# LED-Lamp-pth.net
KiCad netlist of a schematic drawn in EAGLE
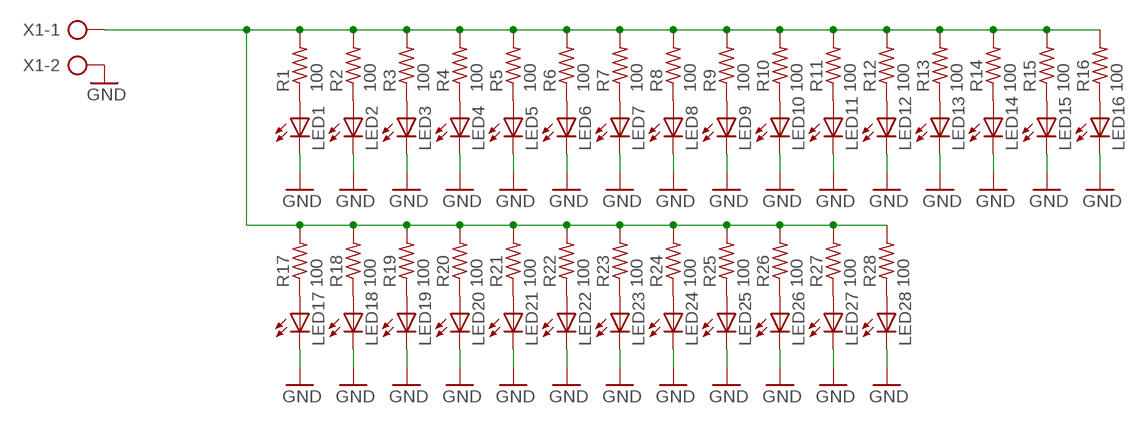
[diagram p0: schematic, sheet 1]

(export (version "E")
  (design (tool "Eeschema 10.0.6"))
  (components
    (comp (ref "LED1")
      (value "LEDSML0805")
      (footprint "eagle-import:SML0805")
      (libsource (lib "eagle-import") (part "LEDSML0805"))
    )
    (comp (ref "LED2")
      (value "LEDSML0805")
      (footprint "eagle-import:SML0805")
      (libsource (lib "eagle-import") (part "LEDSML0805"))
    )
    (comp (ref "LED3")
      (value "LEDSML0805")
      (footprint "eagle-import:SML0805")
      (libsource (lib "eagle-import") (part "LEDSML0805"))
    )
    (comp (ref "LED4")
      (value "LEDSML0805")
      (footprint "eagle-import:SML0805")
      (libsource (lib "eagle-import") (part "LEDSML0805"))
    )
    (comp (ref "LED5")
      (value "LEDSML0805")
      (footprint "eagle-import:SML0805")
      (libsource (lib "eagle-import") (part "LEDSML0805"))
    )
    (comp (ref "LED6")
      (value "LEDSML0805")
      (footprint "eagle-import:SML0805")
      (libsource (lib "eagle-import") (part "LEDSML0805"))
    )
    (comp (ref "LED7")
      (value "LEDSML0805")
      (footprint "eagle-import:SML0805")
      (libsource (lib "eagle-import") (part "LEDSML0805"))
    )
    (comp (ref "LED8")
      (value "LEDSML0805")
      (footprint "eagle-import:SML0805")
      (libsource (lib "eagle-import") (part "LEDSML0805"))
    )
    (comp (ref "LED9")
      (value "LEDSML0805")
      (footprint "eagle-import:SML0805")
      (libsource (lib "eagle-import") (part "LEDSML0805"))
    )
    (comp (ref "LED10")
      (value "LEDSML0805")
      (footprint "eagle-import:SML0805")
      (libsource (lib "eagle-import") (part "LEDSML0805"))
    )
    (comp (ref "LED11")
      (value "LEDSML0805")
      (footprint "eagle-import:SML0805")
      (libsource (lib "eagle-import") (part "LEDSML0805"))
    )
    (comp (ref "LED12")
      (value "LEDSML0805")
      (footprint "eagle-import:SML0805")
      (libsource (lib "eagle-import") (part "LEDSML0805"))
    )
    (comp (ref "LED13")
      (value "LEDSML0805")
      (footprint "eagle-import:SML0805")
      (libsource (lib "eagle-import") (part "LEDSML0805"))
    )
    (comp (ref "LED14")
      (value "LEDSML0805")
      (footprint "eagle-import:SML0805")
      (libsource (lib "eagle-import") (part "LEDSML0805"))
    )
    (comp (ref "LED15")
      (value "LEDSML0805")
      (footprint "eagle-import:SML0805")
      (libsource (lib "eagle-import") (part "LEDSML0805"))
    )
    (comp (ref "LED16")
      (value "LEDSML0805")
      (footprint "eagle-import:SML0805")
      (libsource (lib "eagle-import") (part "LEDSML0805"))
    )
    (comp (ref "LED17")
      (value "LEDSML0805")
      (footprint "eagle-import:SML0805")
      (libsource (lib "eagle-import") (part "LEDSML0805"))
    )
    (comp (ref "LED18")
      (value "LEDSML0805")
      (footprint "eagle-import:SML0805")
      (libsource (lib "eagle-import") (part "LEDSML0805"))
    )
    (comp (ref "LED19")
      (value "LEDSML0805")
      (footprint "eagle-import:SML0805")
      (libsource (lib "eagle-import") (part "LEDSML0805"))
    )
    (comp (ref "LED20")
      (value "LEDSML0805")
      (footprint "eagle-import:SML0805")
      (libsource (lib "eagle-import") (part "LEDSML0805"))
    )
    (comp (ref "LED21")
      (value "LEDSML0805")
      (footprint "eagle-import:SML0805")
      (libsource (lib "eagle-import") (part "LEDSML0805"))
    )
    (comp (ref "LED22")
      (value "LEDSML0805")
      (footprint "eagle-import:SML0805")
      (libsource (lib "eagle-import") (part "LEDSML0805"))
    )
    (comp (ref "LED23")
      (value "LEDSML0805")
      (footprint "eagle-import:SML0805")
      (libsource (lib "eagle-import") (part "LEDSML0805"))
    )
    (comp (ref "LED24")
      (value "LEDSML0805")
      (footprint "eagle-import:SML0805")
      (libsource (lib "eagle-import") (part "LEDSML0805"))
    )
    (comp (ref "LED25")
      (value "LEDSML0805")
      (footprint "eagle-import:SML0805")
      (libsource (lib "eagle-import") (part "LEDSML0805"))
    )
    (comp (ref "LED26")
      (value "LEDSML0805")
      (footprint "eagle-import:SML0805")
      (libsource (lib "eagle-import") (part "LEDSML0805"))
    )
    (comp (ref "LED27")
      (value "LEDSML0805")
      (footprint "eagle-import:SML0805")
      (libsource (lib "eagle-import") (part "LEDSML0805"))
    )
    (comp (ref "LED28")
      (value "LEDSML0805")
      (footprint "eagle-import:SML0805")
      (libsource (lib "eagle-import") (part "LEDSML0805"))
    )
    (comp (ref "R1")
      (value "100")
      (footprint "eagle-import:0207_7")
      (libsource (lib "eagle-import") (part "R-US_0207/7"))
    )
    (comp (ref "R2")
      (value "100")
      (footprint "eagle-import:0207_7")
      (libsource (lib "eagle-import") (part "R-US_0207/7"))
    )
    (comp (ref "R3")
      (value "100")
      (footprint "eagle-import:0207_7")
      (libsource (lib "eagle-import") (part "R-US_0207/7"))
    )
    (comp (ref "R4")
      (value "100")
      (footprint "eagle-import:0207_7")
      (libsource (lib "eagle-import") (part "R-US_0207/7"))
    )
    (comp (ref "R5")
      (value "100")
      (footprint "eagle-import:0207_7")
      (libsource (lib "eagle-import") (part "R-US_0207/7"))
    )
    (comp (ref "R6")
      (value "100")
      (footprint "eagle-import:0207_7")
      (libsource (lib "eagle-import") (part "R-US_0207/7"))
    )
    (comp (ref "R7")
      (value "100")
      (footprint "eagle-import:0207_7")
      (libsource (lib "eagle-import") (part "R-US_0207/7"))
    )
    (comp (ref "R8")
      (value "100")
      (footprint "eagle-import:0207_7")
      (libsource (lib "eagle-import") (part "R-US_0207/7"))
    )
    (comp (ref "R9")
      (value "100")
      (footprint "eagle-import:0207_7")
      (libsource (lib "eagle-import") (part "R-US_0207/7"))
    )
    (comp (ref "R10")
      (value "100")
      (footprint "eagle-import:0207_7")
      (libsource (lib "eagle-import") (part "R-US_0207/7"))
    )
    (comp (ref "R11")
      (value "100")
      (footprint "eagle-import:0207_7")
      (libsource (lib "eagle-import") (part "R-US_0207/7"))
    )
    (comp (ref "R12")
      (value "100")
      (footprint "eagle-import:0207_7")
      (libsource (lib "eagle-import") (part "R-US_0207/7"))
    )
    (comp (ref "R13")
      (value "100")
      (footprint "eagle-import:0207_7")
      (libsource (lib "eagle-import") (part "R-US_0207/7"))
    )
    (comp (ref "R14")
      (value "100")
      (footprint "eagle-import:0207_7")
      (libsource (lib "eagle-import") (part "R-US_0207/7"))
    )
    (comp (ref "R15")
      (value "100")
      (footprint "eagle-import:0207_7")
      (libsource (lib "eagle-import") (part "R-US_0207/7"))
    )
    (comp (ref "R16")
      (value "100")
      (footprint "eagle-import:0207_7")
      (libsource (lib "eagle-import") (part "R-US_0207/7"))
    )
    (comp (ref "R17")
      (value "100")
      (footprint "eagle-import:0207_7")
      (libsource (lib "eagle-import") (part "R-US_0207/7"))
    )
    (comp (ref "R18")
      (value "100")
      (footprint "eagle-import:0207_7")
      (libsource (lib "eagle-import") (part "R-US_0207/7"))
    )
    (comp (ref "R19")
      (value "100")
      (footprint "eagle-import:0207_7")
      (libsource (lib "eagle-import") (part "R-US_0207/7"))
    )
    (comp (ref "R20")
      (value "100")
      (footprint "eagle-import:0207_7")
      (libsource (lib "eagle-import") (part "R-US_0207/7"))
    )
    (comp (ref "R21")
      (value "100")
      (footprint "eagle-import:0207_7")
      (libsource (lib "eagle-import") (part "R-US_0207/7"))
    )
    (comp (ref "R22")
      (value "100")
      (footprint "eagle-import:0207_7")
      (libsource (lib "eagle-import") (part "R-US_0207/7"))
    )
    (comp (ref "R23")
      (value "100")
      (footprint "eagle-import:0207_7")
      (libsource (lib "eagle-import") (part "R-US_0207/7"))
    )
    (comp (ref "R24")
      (value "100")
      (footprint "eagle-import:0207_7")
      (libsource (lib "eagle-import") (part "R-US_0207/7"))
    )
    (comp (ref "R25")
      (value "100")
      (footprint "eagle-import:0207_7")
      (libsource (lib "eagle-import") (part "R-US_0207/7"))
    )
    (comp (ref "R26")
      (value "100")
      (footprint "eagle-import:0207_7")
      (libsource (lib "eagle-import") (part "R-US_0207/7"))
    )
    (comp (ref "R27")
      (value "100")
      (footprint "eagle-import:0207_7")
      (libsource (lib "eagle-import") (part "R-US_0207/7"))
    )
    (comp (ref "R28")
      (value "100")
      (footprint "eagle-import:0207_7")
      (libsource (lib "eagle-import") (part "R-US_0207/7"))
    )
    (comp (ref "X1")
      (value "AK300/2")
      (footprint "eagle-import:AK300_2")
      (libsource (lib "eagle-import") (part "AK300/2"))
    )
  )
  (nets
    (net (code "1") (name "GND") (class "Default")
      (node (ref "LED1") (pin "C") (pinfunction "C_C") (pintype "passive"))
      (node (ref "LED10") (pin "C") (pinfunction "C_C") (pintype "passive"))
      (node (ref "LED11") (pin "C") (pinfunction "C_C") (pintype "passive"))
      (node (ref "LED12") (pin "C") (pinfunction "C_C") (pintype "passive"))
      (node (ref "LED13") (pin "C") (pinfunction "C_C") (pintype "passive"))
      (node (ref "LED14") (pin "C") (pinfunction "C_C") (pintype "passive"))
      (node (ref "LED15") (pin "C") (pinfunction "C_C") (pintype "passive"))
      (node (ref "LED16") (pin "C") (pinfunction "C_C") (pintype "passive"))
      (node (ref "LED17") (pin "C") (pinfunction "C_C") (pintype "passive"))
      (node (ref "LED18") (pin "C") (pinfunction "C_C") (pintype "passive"))
      (node (ref "LED19") (pin "C") (pinfunction "C_C") (pintype "passive"))
      (node (ref "LED2") (pin "C") (pinfunction "C_C") (pintype "passive"))
      (node (ref "LED20") (pin "C") (pinfunction "C_C") (pintype "passive"))
      (node (ref "LED21") (pin "C") (pinfunction "C_C") (pintype "passive"))
      (node (ref "LED22") (pin "C") (pinfunction "C_C") (pintype "passive"))
      (node (ref "LED23") (pin "C") (pinfunction "C_C") (pintype "passive"))
      (node (ref "LED24") (pin "C") (pinfunction "C_C") (pintype "passive"))
      (node (ref "LED25") (pin "C") (pinfunction "C_C") (pintype "passive"))
      (node (ref "LED26") (pin "C") (pinfunction "C_C") (pintype "passive"))
      (node (ref "LED27") (pin "C") (pinfunction "C_C") (pintype "passive"))
      (node (ref "LED28") (pin "C") (pinfunction "C_C") (pintype "passive"))
      (node (ref "LED3") (pin "C") (pinfunction "C_C") (pintype "passive"))
      (node (ref "LED4") (pin "C") (pinfunction "C_C") (pintype "passive"))
      (node (ref "LED5") (pin "C") (pinfunction "C_C") (pintype "passive"))
      (node (ref "LED6") (pin "C") (pinfunction "C_C") (pintype "passive"))
      (node (ref "LED7") (pin "C") (pinfunction "C_C") (pintype "passive"))
      (node (ref "LED8") (pin "C") (pinfunction "C_C") (pintype "passive"))
      (node (ref "LED9") (pin "C") (pinfunction "C_C") (pintype "passive"))
      (node (ref "X1") (pin "2") (pinfunction "KL_2") (pintype "passive"))
    )
    (net (code "2") (name "Net-(LED1-PadA)") (class "Default")
      (node (ref "LED1") (pin "A") (pinfunction "A_A") (pintype "passive"))
      (node (ref "R1") (pin "1") (pinfunction "1_1") (pintype "passive"))
    )
    (net (code "3") (name "Net-(LED2-PadA)") (class "Default")
      (node (ref "LED2") (pin "A") (pinfunction "A_A") (pintype "passive"))
      (node (ref "R2") (pin "1") (pinfunction "1_1") (pintype "passive"))
    )
    (net (code "4") (name "Net-(LED3-PadA)") (class "Default")
      (node (ref "LED3") (pin "A") (pinfunction "A_A") (pintype "passive"))
      (node (ref "R3") (pin "1") (pinfunction "1_1") (pintype "passive"))
    )
    (net (code "5") (name "Net-(LED4-PadA)") (class "Default")
      (node (ref "LED4") (pin "A") (pinfunction "A_A") (pintype "passive"))
      (node (ref "R4") (pin "1") (pinfunction "1_1") (pintype "passive"))
    )
    (net (code "6") (name "Net-(LED5-PadA)") (class "Default")
      (node (ref "LED5") (pin "A") (pinfunction "A_A") (pintype "passive"))
      (node (ref "R5") (pin "1") (pinfunction "1_1") (pintype "passive"))
    )
    (net (code "7") (name "Net-(LED6-PadA)") (class "Default")
      (node (ref "LED6") (pin "A") (pinfunction "A_A") (pintype "passive"))
      (node (ref "R6") (pin "1") (pinfunction "1_1") (pintype "passive"))
    )
    (net (code "8") (name "Net-(LED7-PadA)") (class "Default")
      (node (ref "LED7") (pin "A") (pinfunction "A_A") (pintype "passive"))
      (node (ref "R7") (pin "1") (pinfunction "1_1") (pintype "passive"))
    )
    (net (code "9") (name "Net-(LED8-PadA)") (class "Default")
      (node (ref "LED8") (pin "A") (pinfunction "A_A") (pintype "passive"))
      (node (ref "R8") (pin "1") (pinfunction "1_1") (pintype "passive"))
    )
    (net (code "10") (name "Net-(LED9-PadA)") (class "Default")
      (node (ref "LED9") (pin "A") (pinfunction "A_A") (pintype "passive"))
      (node (ref "R9") (pin "1") (pinfunction "1_1") (pintype "passive"))
    )
    (net (code "11") (name "Net-(LED10-PadA)") (class "Default")
      (node (ref "LED10") (pin "A") (pinfunction "A_A") (pintype "passive"))
      (node (ref "R10") (pin "1") (pinfunction "1_1") (pintype "passive"))
    )
    (net (code "12") (name "Net-(LED11-PadA)") (class "Default")
      (node (ref "LED11") (pin "A") (pinfunction "A_A") (pintype "passive"))
      (node (ref "R11") (pin "1") (pinfunction "1_1") (pintype "passive"))
    )
    (net (code "13") (name "Net-(LED12-PadA)") (class "Default")
      (node (ref "LED12") (pin "A") (pinfunction "A_A") (pintype "passive"))
      (node (ref "R12") (pin "1") (pinfunction "1_1") (pintype "passive"))
    )
    (net (code "14") (name "Net-(LED13-PadA)") (class "Default")
      (node (ref "LED13") (pin "A") (pinfunction "A_A") (pintype "passive"))
      (node (ref "R13") (pin "1") (pinfunction "1_1") (pintype "passive"))
    )
    (net (code "15") (name "Net-(LED14-PadA)") (class "Default")
      (node (ref "LED14") (pin "A") (pinfunction "A_A") (pintype "passive"))
      (node (ref "R14") (pin "1") (pinfunction "1_1") (pintype "passive"))
    )
    (net (code "16") (name "Net-(LED15-PadA)") (class "Default")
      (node (ref "LED15") (pin "A") (pinfunction "A_A") (pintype "passive"))
      (node (ref "R15") (pin "1") (pinfunction "1_1") (pintype "passive"))
    )
    (net (code "17") (name "Net-(LED16-PadA)") (class "Default")
      (node (ref "LED16") (pin "A") (pinfunction "A_A") (pintype "passive"))
      (node (ref "R16") (pin "1") (pinfunction "1_1") (pintype "passive"))
    )
    (net (code "18") (name "Net-(LED17-PadA)") (class "Default")
      (node (ref "LED17") (pin "A") (pinfunction "A_A") (pintype "passive"))
      (node (ref "R17") (pin "1") (pinfunction "1_1") (pintype "passive"))
    )
    (net (code "19") (name "Net-(LED18-PadA)") (class "Default")
      (node (ref "LED18") (pin "A") (pinfunction "A_A") (pintype "passive"))
      (node (ref "R18") (pin "1") (pinfunction "1_1") (pintype "passive"))
    )
    (net (code "20") (name "Net-(LED19-PadA)") (class "Default")
      (node (ref "LED19") (pin "A") (pinfunction "A_A") (pintype "passive"))
      (node (ref "R19") (pin "1") (pinfunction "1_1") (pintype "passive"))
    )
    (net (code "21") (name "Net-(LED20-PadA)") (class "Default")
      (node (ref "LED20") (pin "A") (pinfunction "A_A") (pintype "passive"))
      (node (ref "R20") (pin "1") (pinfunction "1_1") (pintype "passive"))
    )
    (net (code "22") (name "Net-(LED21-PadA)") (class "Default")
      (node (ref "LED21") (pin "A") (pinfunction "A_A") (pintype "passive"))
      (node (ref "R21") (pin "1") (pinfunction "1_1") (pintype "passive"))
    )
    (net (code "23") (name "Net-(LED22-PadA)") (class "Default")
      (node (ref "LED22") (pin "A") (pinfunction "A_A") (pintype "passive"))
      (node (ref "R22") (pin "1") (pinfunction "1_1") (pintype "passive"))
    )
    (net (code "24") (name "Net-(LED23-PadA)") (class "Default")
      (node (ref "LED23") (pin "A") (pinfunction "A_A") (pintype "passive"))
      (node (ref "R23") (pin "1") (pinfunction "1_1") (pintype "passive"))
    )
    (net (code "25") (name "Net-(LED24-PadA)") (class "Default")
      (node (ref "LED24") (pin "A") (pinfunction "A_A") (pintype "passive"))
      (node (ref "R24") (pin "1") (pinfunction "1_1") (pintype "passive"))
    )
    (net (code "26") (name "Net-(LED25-PadA)") (class "Default")
      (node (ref "LED25") (pin "A") (pinfunction "A_A") (pintype "passive"))
      (node (ref "R25") (pin "1") (pinfunction "1_1") (pintype "passive"))
    )
    (net (code "27") (name "Net-(LED26-PadA)") (class "Default")
      (node (ref "LED26") (pin "A") (pinfunction "A_A") (pintype "passive"))
      (node (ref "R26") (pin "1") (pinfunction "1_1") (pintype "passive"))
    )
    (net (code "28") (name "Net-(LED27-PadA)") (class "Default")
      (node (ref "LED27") (pin "A") (pinfunction "A_A") (pintype "passive"))
      (node (ref "R27") (pin "1") (pinfunction "1_1") (pintype "passive"))
    )
    (net (code "29") (name "Net-(LED28-PadA)") (class "Default")
      (node (ref "LED28") (pin "A") (pinfunction "A_A") (pintype "passive"))
      (node (ref "R28") (pin "1") (pinfunction "1_1") (pintype "passive"))
    )
    (net (code "30") (name "Net-(X1A-KL)") (class "Default")
      (node (ref "R1") (pin "2") (pinfunction "2_2") (pintype "passive"))
      (node (ref "R10") (pin "2") (pinfunction "2_2") (pintype "passive"))
      (node (ref "R11") (pin "2") (pinfunction "2_2") (pintype "passive"))
      (node (ref "R12") (pin "2") (pinfunction "2_2") (pintype "passive"))
      (node (ref "R13") (pin "2") (pinfunction "2_2") (pintype "passive"))
      (node (ref "R14") (pin "2") (pinfunction "2_2") (pintype "passive"))
      (node (ref "R15") (pin "2") (pinfunction "2_2") (pintype "passive"))
      (node (ref "R16") (pin "2") (pinfunction "2_2") (pintype "passive"))
      (node (ref "R17") (pin "2") (pinfunction "2_2") (pintype "passive"))
      (node (ref "R18") (pin "2") (pinfunction "2_2") (pintype "passive"))
      (node (ref "R19") (pin "2") (pinfunction "2_2") (pintype "passive"))
      (node (ref "R2") (pin "2") (pinfunction "2_2") (pintype "passive"))
      (node (ref "R20") (pin "2") (pinfunction "2_2") (pintype "passive"))
      (node (ref "R21") (pin "2") (pinfunction "2_2") (pintype "passive"))
      (node (ref "R22") (pin "2") (pinfunction "2_2") (pintype "passive"))
      (node (ref "R23") (pin "2") (pinfunction "2_2") (pintype "passive"))
      (node (ref "R24") (pin "2") (pinfunction "2_2") (pintype "passive"))
      (node (ref "R25") (pin "2") (pinfunction "2_2") (pintype "passive"))
      (node (ref "R26") (pin "2") (pinfunction "2_2") (pintype "passive"))
      (node (ref "R27") (pin "2") (pinfunction "2_2") (pintype "passive"))
      (node (ref "R28") (pin "2") (pinfunction "2_2") (pintype "passive"))
      (node (ref "R3") (pin "2") (pinfunction "2_2") (pintype "passive"))
      (node (ref "R4") (pin "2") (pinfunction "2_2") (pintype "passive"))
      (node (ref "R5") (pin "2") (pinfunction "2_2") (pintype "passive"))
      (node (ref "R6") (pin "2") (pinfunction "2_2") (pintype "passive"))
      (node (ref "R7") (pin "2") (pinfunction "2_2") (pintype "passive"))
      (node (ref "R8") (pin "2") (pinfunction "2_2") (pintype "passive"))
      (node (ref "R9") (pin "2") (pinfunction "2_2") (pintype "passive"))
      (node (ref "X1") (pin "1") (pinfunction "KL_1") (pintype "passive"))
    )
  )
)
